# Voltage_Step_Up_Regulator.net
KiCad netlist of a schematic drawn in Altium Designer
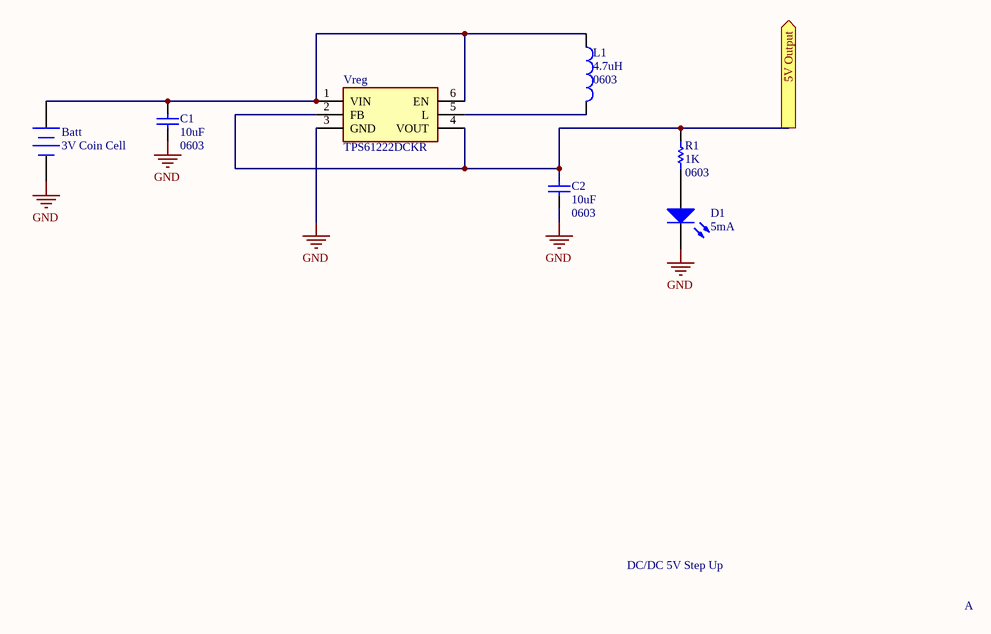
[diagram p0: Voltage Step Up Regulator.SchDoc]

(export (version "E")
  (design (tool "Eeschema 10.0.6"))
  (components
    (comp (ref "Batt")
      (value "3V Coin Cell")
      (footprint "*BAT_BU2032SM-JJ-GTR_BU2032SM-JJ-GTR(Primary)")
      (description "Multicell Battery")
      (fields (field (name "PUBLISHER") "Altium Limited"))
      (libsource (lib "Miscellaneous Devices") (part "Battery"))
    )
    (comp (ref "C1")
      (value "10uF")
      (footprint "SMD-0603C")
      (description "Capacitor")
      (fields (field (name "ALTIUM_VALUE") "0603") (field (name "PUBLISHER") "Altium Limited"))
      (libsource (lib "Miscellaneous Devices") (part "Cap"))
    )
    (comp (ref "C2")
      (value "10uF")
      (footprint "SMD-0603C")
      (description "Capacitor")
      (fields (field (name "ALTIUM_VALUE") "0603") (field (name "PUBLISHER") "Altium Limited"))
      (libsource (lib "Miscellaneous Devices") (part "Cap"))
    )
    (comp (ref "D1")
      (value "5mA")
      (footprint "*0603")
      (description "Typical INFRARED GaAs LED")
      (fields (field (name "PUBLISHER") "Altium Limited"))
      (libsource (lib "Miscellaneous Devices") (part "LED0"))
    )
    (comp (ref "L1")
      (value "4.7uH")
      (footprint "INDC1608L")
      (description "Inductor")
      (fields (field (name "ALTIUM_VALUE") "0603") (field (name "PUBLISHER") "Altium Limited"))
      (libsource (lib "Miscellaneous Devices") (part "Inductor"))
    )
    (comp (ref "R1")
      (value "1K")
      (footprint "SMD-0603-RES")
      (description "Resistor")
      (fields (field (name "ALTIUM_VALUE") "0603") (field (name "PUBLISHER") "Altium Limited"))
      (libsource (lib "Miscellaneous Devices") (part "Res1"))
    )
    (comp (ref "Vreg")
      (value "TPS61222DCKR")
      (footprint "*TPS61221_TPS61221(Primary)")
      (description "Integrated Circuit")
      (fields (field (name "MOUSER PART NUMBER") "595-TPS61222DCKR"))
      (libsource (lib "*") (part "TPS61222DCKR"))
    )
  )
  (nets
    (net (code "1") (name "/5V Output") (class "Default")
      (node (ref "C2") (pin "1") (pinfunction "1_1") (pintype "passive"))
      (node (ref "R1") (pin "1") (pinfunction "1_1") (pintype "passive"))
      (node (ref "Vreg") (pin "2") (pinfunction "FB_2") (pintype "passive"))
      (node (ref "Vreg") (pin "4") (pinfunction "VOUT_4") (pintype "passive"))
    )
    (net (code "2") (name "GND") (class "Default")
      (node (ref "Batt") (pin "2") (pinfunction "-_2") (pintype "passive"))
      (node (ref "C1") (pin "2") (pinfunction "2_2") (pintype "passive"))
      (node (ref "C2") (pin "2") (pinfunction "2_2") (pintype "passive"))
      (node (ref "D1") (pin "2") (pinfunction "K_2") (pintype "passive"))
      (node (ref "Vreg") (pin "3") (pinfunction "GND_3") (pintype "passive"))
    )
    (net (code "3") (name "Net-(Batt-+)") (class "Default")
      (node (ref "Batt") (pin "1") (pinfunction "+_1") (pintype "passive"))
      (node (ref "C1") (pin "1") (pinfunction "1_1") (pintype "passive"))
      (node (ref "L1") (pin "1") (pinfunction "1_1") (pintype "passive"))
      (node (ref "Vreg") (pin "1") (pinfunction "VIN_1") (pintype "passive"))
      (node (ref "Vreg") (pin "6") (pinfunction "EN_6") (pintype "passive"))
    )
    (net (code "4") (name "Net-(D1-A)") (class "Default")
      (node (ref "D1") (pin "1") (pinfunction "A_1") (pintype "passive"))
      (node (ref "R1") (pin "2") (pinfunction "2_2") (pintype "passive"))
    )
    (net (code "5") (name "Net-(Vreg-L)") (class "Default")
      (node (ref "L1") (pin "2") (pinfunction "2_2") (pintype "passive"))
      (node (ref "Vreg") (pin "5") (pinfunction "L_5") (pintype "passive"))
    )
  )
)
